# mainSchematic.net
KiCad netlist of a schematic drawn in Altium Designer
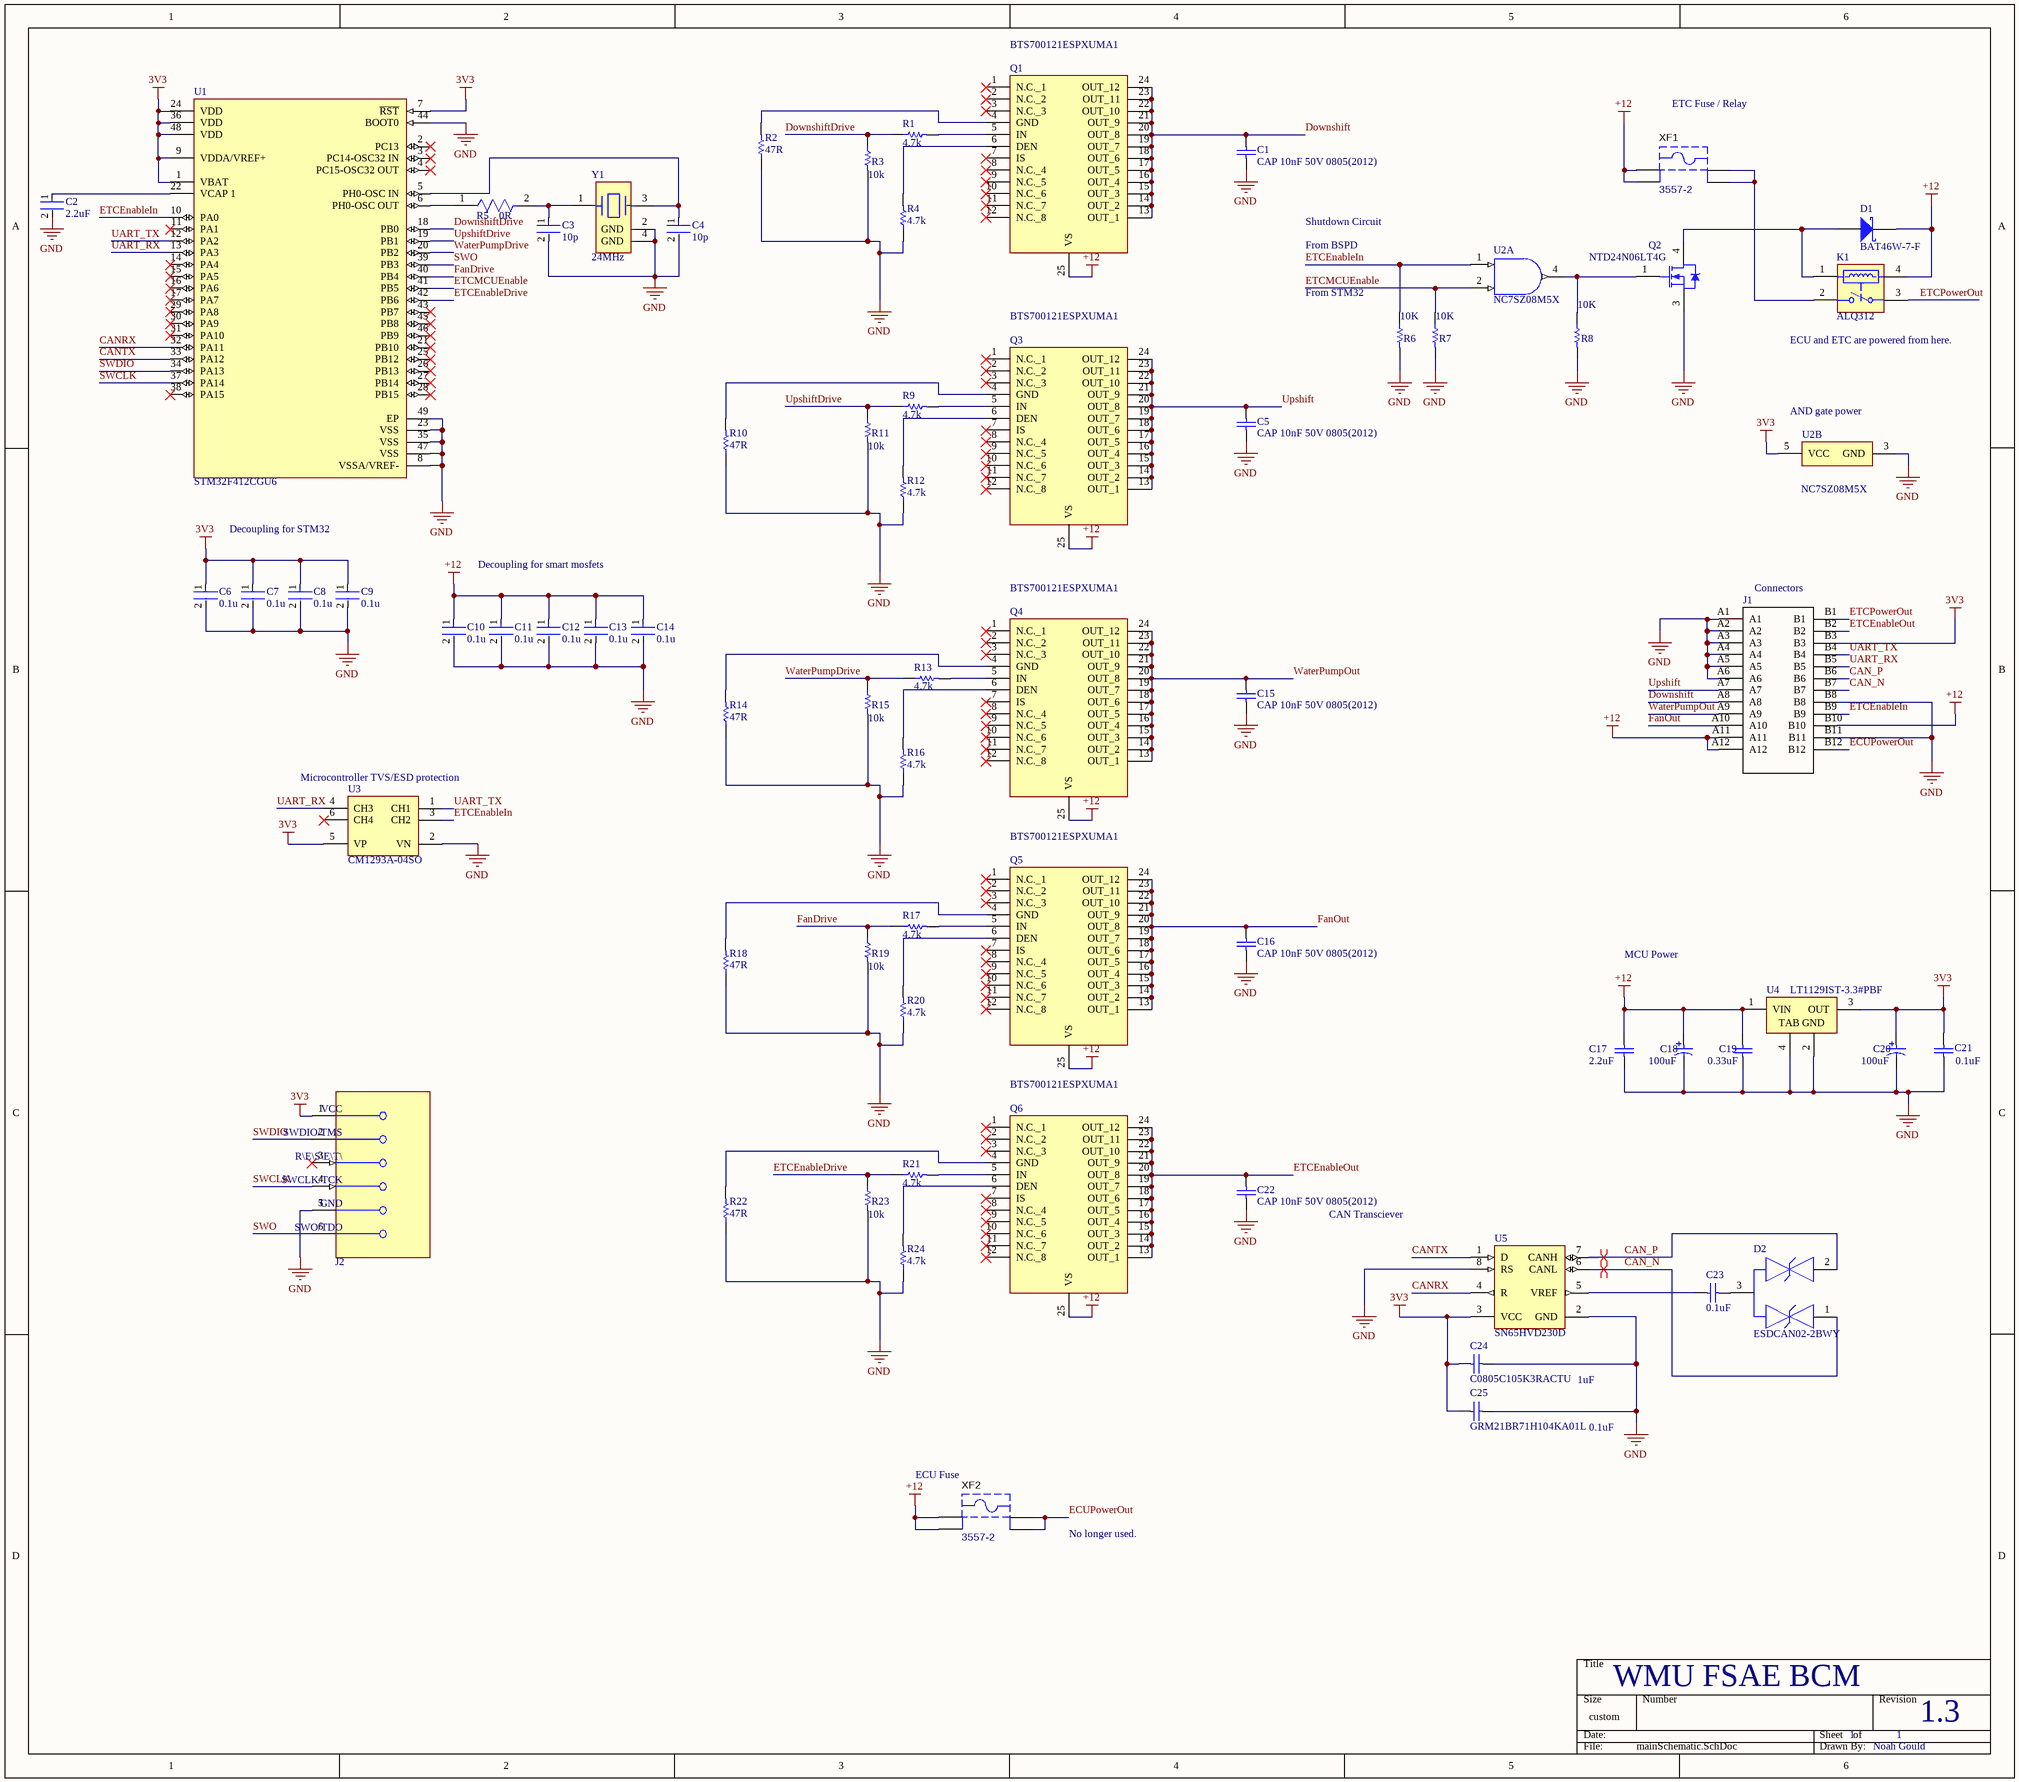
[diagram p0: mainSchematic.SchDoc]

(export (version "E")
  (design (tool "Eeschema 10.0.6"))
  (components
    (comp (ref "C1")
      (value "CAP 10nF 50V 0805(2012)")
      (footprint "CAPC0805(2012)75_N")
      (description "CAP 10nF 50V ±5% 0805 (2012 Metric) Thickness 0.75mm SMD")
      (fields (field (name "TOLERANCE") "Â±5%"))
      (libsource (lib "Altium Content Vault") (part "CAP"))
    )
    (comp (ref "C2")
      (value "2.2uF")
      (footprint "FP-GRM188-0_1-e0_2_0_5-MFG")
      (description "Chip Multilayer Ceramic Capacitors for General Purpose, 0603, 2.2uF, X7R, 15%, 10%, 10V")
      (fields (field (name "VOLTAGE") "10V") (field (name "TOLERANCE") "10%"))
      (libsource (lib "Altium Content Vault") (part "11868f565c42a9108669ba33697ecf6"))
    )
    (comp (ref "C3")
      (value "10p")
      (footprint "FP-0603-L_1_6_0_15-W_0_81-IPC_C")
      (description "General Purpose Ceramic Capacitor, 0603, 10pF, 10%, NP0, 30ppm/°C, 50V")
      (fields (field (name "TOLERANCE") "10%") (field (name "VOLTAGE") "50V"))
      (libsource (lib "Altium Content Vault") (part "02cd4be3c70576c341d710602a673aa"))
    )
    (comp (ref "C4")
      (value "10p")
      (footprint "FP-0603-L_1_6_0_15-W_0_81-IPC_C")
      (description "General Purpose Ceramic Capacitor, 0603, 10pF, 10%, NP0, 30ppm/°C, 50V")
      (fields (field (name "TOLERANCE") "10%") (field (name "VOLTAGE") "50V"))
      (libsource (lib "Altium Content Vault") (part "02cd4be3c70576c341d710602a673aa"))
    )
    (comp (ref "C5")
      (value "CAP 10nF 50V 0805(2012)")
      (footprint "CAPC0805(2012)75_N")
      (description "CAP 10nF 50V ±5% 0805 (2012 Metric) Thickness 0.75mm SMD")
      (fields (field (name "TOLERANCE") "Â±5%"))
      (libsource (lib "Altium Content Vault") (part "CAP"))
    )
    (comp (ref "C6")
      (value "0.1u")
      (footprint "FP-C0603C-CF-MFG")
      (description "CAP CER 0.1UF 50V X7R 0603")
      (fields (field (name "TOLERANCE") "0.1") (field (name "MANUFACTURER") "KEMET"))
      (libsource (lib "Altium Content Vault") (part "b4654b650e69147ec39a6b967a45e02"))
    )
    (comp (ref "C7")
      (value "0.1u")
      (footprint "FP-C0603C-CF-MFG")
      (description "CAP CER 0.1UF 50V X7R 0603")
      (fields (field (name "TOLERANCE") "0.1") (field (name "MANUFACTURER") "KEMET"))
      (libsource (lib "Altium Content Vault") (part "b4654b650e69147ec39a6b967a45e02"))
    )
    (comp (ref "C8")
      (value "0.1u")
      (footprint "FP-C0603C-CF-MFG")
      (description "CAP CER 0.1UF 50V X7R 0603")
      (fields (field (name "TOLERANCE") "0.1") (field (name "MANUFACTURER") "KEMET"))
      (libsource (lib "Altium Content Vault") (part "b4654b650e69147ec39a6b967a45e02"))
    )
    (comp (ref "C9")
      (value "0.1u")
      (footprint "FP-C0603C-CF-MFG")
      (description "CAP CER 0.1UF 50V X7R 0603")
      (fields (field (name "TOLERANCE") "0.1") (field (name "MANUFACTURER") "KEMET"))
      (libsource (lib "Altium Content Vault") (part "b4654b650e69147ec39a6b967a45e02"))
    )
    (comp (ref "C10")
      (value "0.1u")
      (footprint "FP-C0603C-CF-MFG")
      (description "CAP CER 0.1UF 50V X7R 0603")
      (fields (field (name "TOLERANCE") "0.1") (field (name "MANUFACTURER") "KEMET"))
      (libsource (lib "Altium Content Vault") (part "b4654b650e69147ec39a6b967a45e02"))
    )
    (comp (ref "C11")
      (value "0.1u")
      (footprint "FP-C0603C-CF-MFG")
      (description "CAP CER 0.1UF 50V X7R 0603")
      (fields (field (name "TOLERANCE") "0.1") (field (name "MANUFACTURER") "KEMET"))
      (libsource (lib "Altium Content Vault") (part "b4654b650e69147ec39a6b967a45e02"))
    )
    (comp (ref "C12")
      (value "0.1u")
      (footprint "FP-C0603C-CF-MFG")
      (description "CAP CER 0.1UF 50V X7R 0603")
      (fields (field (name "TOLERANCE") "0.1") (field (name "MANUFACTURER") "KEMET"))
      (libsource (lib "Altium Content Vault") (part "b4654b650e69147ec39a6b967a45e02"))
    )
    (comp (ref "C13")
      (value "0.1u")
      (footprint "FP-C0603C-CF-MFG")
      (description "CAP CER 0.1UF 50V X7R 0603")
      (fields (field (name "TOLERANCE") "0.1") (field (name "MANUFACTURER") "KEMET"))
      (libsource (lib "Altium Content Vault") (part "b4654b650e69147ec39a6b967a45e02"))
    )
    (comp (ref "C14")
      (value "0.1u")
      (footprint "FP-C0603C-CF-MFG")
      (description "CAP CER 0.1UF 50V X7R 0603")
      (fields (field (name "TOLERANCE") "0.1") (field (name "MANUFACTURER") "KEMET"))
      (libsource (lib "Altium Content Vault") (part "b4654b650e69147ec39a6b967a45e02"))
    )
    (comp (ref "C15")
      (value "CAP 10nF 50V 0805(2012)")
      (footprint "CAPC0805(2012)75_N")
      (description "CAP 10nF 50V ±5% 0805 (2012 Metric) Thickness 0.75mm SMD")
      (fields (field (name "TOLERANCE") "Â±5%"))
      (libsource (lib "Altium Content Vault") (part "CAP"))
    )
    (comp (ref "C16")
      (value "CAP 10nF 50V 0805(2012)")
      (footprint "CAPC0805(2012)75_N")
      (description "CAP 10nF 50V ±5% 0805 (2012 Metric) Thickness 0.75mm SMD")
      (fields (field (name "TOLERANCE") "Â±5%"))
      (libsource (lib "Altium Content Vault") (part "CAP"))
    )
    (comp (ref "C17")
      (value "CAP 2.2uF 100V 1210(3225)")
      (footprint "CAPC1210(3225)280_N")
      (description "CAP 2.2uF 100V ±10% 1210 (3225 Metric) Thickness 2.8mm SMD")
      (fields (field (name "TOLERANCE") "Â±10%"))
      (libsource (lib "Altium Content Vault") (part "CAP"))
    )
    (comp (ref "C18")
      (value "EEEFK1H101P")
      (footprint "PNSC-FK-V-F_V")
      (fields (field (name "MANUFACTURER") "Panasonic"))
      (libsource (lib "Altium Content Vault") (part "CAP-P-2"))
    )
    (comp (ref "C19")
      (value "12065C334KAT2A")
      (footprint "CAPC3216X152X50LL20T25")
      (description "Chip Capacitor, 330 nF, +/- 10%, 50 V, -55 to 125 degC, 1206 (3216 Metric), RoHS, Tape and Reel")
      (fields (field (name "MANUFACTURER") "AVX"))
      (libsource (lib "Altium Content Vault") (part "CAP-NP-2"))
    )
    (comp (ref "C20")
      (value "EEEFK1H101P")
      (footprint "PNSC-FK-V-F_V")
      (fields (field (name "MANUFACTURER") "Panasonic"))
      (libsource (lib "Altium Content Vault") (part "CAP-P-2"))
    )
    (comp (ref "C21")
      (value "GRM21BR71H104KA01L")
      (footprint "CAPC2013X135X45ML10T25")
      (description "Chip Capacitor, 0.1 uF, +/- 10%, 50 V, -55 to 125 degC, 0805 (2012 Metric), RoHS, Tape and Reel")
      (fields (field (name "VOLTAGE") "50V") (field (name "TOLERANCE") "10%"))
      (libsource (lib "Altium Content Vault") (part "CAP-NP-2"))
    )
    (comp (ref "C22")
      (value "CAP 10nF 50V 0805(2012)")
      (footprint "CAPC0805(2012)75_N")
      (description "CAP 10nF 50V ±5% 0805 (2012 Metric) Thickness 0.75mm SMD")
      (fields (field (name "TOLERANCE") "Â±5%"))
      (libsource (lib "Altium Content Vault") (part "CAP"))
    )
    (comp (ref "C23")
      (value "0.1uF")
      (footprint "CAPC2013X135X45ML10T25")
      (description "Chip Capacitor, 0.1 uF, +/- 10%, 50 V, -55 to 125 degC, 0805 (2012 Metric), RoHS, Tape and Reel")
      (fields (field (name "VOLTAGE") "50V") (field (name "TOLERANCE") "10%"))
      (libsource (lib "Altium Content Vault") (part "CAP-NP-2"))
    )
    (comp (ref "C24")
      (value "C0805C105K3RACTU")
      (footprint "CAPC2013X140X50LL20T25")
      (fields (field (name "MANUFACTURER") "Kemet"))
      (libsource (lib "Altium Content Vault") (part "CAP"))
    )
    (comp (ref "C25")
      (value "GRM21BR71H104KA01L")
      (footprint "CAPC2013X135X45ML10T25")
      (description "Chip Capacitor, 0.1 uF, +/- 10%, 50 V, -55 to 125 degC, 0805 (2012 Metric), RoHS, Tape and Reel")
      (fields (field (name "VOLTAGE") "50V") (field (name "TOLERANCE") "10%"))
      (libsource (lib "Altium Content Vault") (part "CAP-NP-2"))
    )
    (comp (ref "D1")
      (value "BAT46W-7-F")
      (footprint "DIOD-SOD-123-2_V")
      (description "Surface Mount Schottky Barrier Diode, 100 V, -55 to 125 degC, 2-Pin SOD123, RoHS, Tape and Reel")
      (fields (field (name "MANUFACTURER") "Diodes Inc"))
      (libsource (lib "Altium Content Vault") (part "DIOD-DSKY-A1K2-2"))
    )
    (comp (ref "D2")
      (value "ESDCAN02-2BWY")
      (footprint "FP-SOT323-3L-MFG")
      (description "TVS DIODE 26.5V 44V SOT323-3")
      (fields
        (field (name "MANUFACTURER") "STMicroelectronics")
        (field (name "OCTOPART") "https://octopart.com/esdcan02-2bwy-stmicroelectronics-58631133")
      )
      (libsource (lib "Altium Content Vault") (part "0b9019fb5e52ed66df21ec1535be59d"))
    )
    (comp (ref "J1")
      (value "DTM1312PA12PBR008")
      (footprint "*TE_DTM1312PA12PBR008_DTM1312PA12PBR008(Primary)")
      (description "Double Header 24 pin receptacle")
      (fields (field (name "MP") "DTM13-12PA-12PB-R008") (field (name "MF") "TE Connectivity"))
      (libsource (lib "DTM1312PA12PBR008") (part "DTM1312PA12PBR008"))
    )
    (comp (ref "J2")
      (value "TC2030-CTX-NL")
      (footprint "Tag_Connect_0_MFG")
      (libsource (lib "Conn_Tag_Connect_TC2030-CTX-NL_eec") (part "TC2030-CTX-NL"))
    )
    (comp (ref "K1")
      (value "ALQ312")
      (footprint "PNSC-LQ-4-2000x1000x1600_V")
      (fields (field (name "MANUFACTURER") "Panasonic"))
      (libsource (lib "Altium Content Vault") (part "PNSC-ALQ312-LQ-4-2000x1000x1600-4"))
    )
    (comp (ref "Q1")
      (value "BTS700121ESPXUMA1")
      (footprint "SamacSys:SOP65P600X115-25N")
      (description "Integrated Circuit")
      (fields (field (name "MOUSER PART NUMBER") "726-BTS700121ESPXUMA"))
      (libsource (lib "*") (part "BTS700121ESPXUMA1"))
    )
    (comp (ref "Q2")
      (value "NTD24N06LT4G")
      (footprint "ONSC-DPAK-3-369C-01_V")
      (description "Power MOSFET, 24 A, 60 V, Logic Level, N-Channel, 3-Pin DPAK, Pb-Free, Tape and Reel")
      (fields (field (name "MANUFACTURER") "On Semiconductor"))
      (libsource (lib "Altium Content Vault") (part "ONSC-NMOS-G1S3D4-3_C"))
    )
    (comp (ref "Q3")
      (value "BTS700121ESPXUMA1")
      (footprint "SamacSys:SOP65P600X115-25N")
      (description "Integrated Circuit")
      (fields (field (name "MOUSER PART NUMBER") "726-BTS700121ESPXUMA"))
      (libsource (lib "*") (part "BTS700121ESPXUMA1"))
    )
    (comp (ref "Q4")
      (value "BTS700121ESPXUMA1")
      (footprint "SamacSys:SOP65P600X115-25N")
      (description "Integrated Circuit")
      (fields (field (name "MOUSER PART NUMBER") "726-BTS700121ESPXUMA"))
      (libsource (lib "*") (part "BTS700121ESPXUMA1"))
    )
    (comp (ref "Q5")
      (value "BTS700121ESPXUMA1")
      (footprint "SamacSys:SOP65P600X115-25N")
      (description "Integrated Circuit")
      (fields (field (name "MOUSER PART NUMBER") "726-BTS700121ESPXUMA"))
      (libsource (lib "*") (part "BTS700121ESPXUMA1"))
    )
    (comp (ref "Q6")
      (value "BTS700121ESPXUMA1")
      (footprint "SamacSys:SOP65P600X115-25N")
      (description "Integrated Circuit")
      (fields (field (name "MOUSER PART NUMBER") "726-BTS700121ESPXUMA"))
      (libsource (lib "*") (part "BTS700121ESPXUMA1"))
    )
    (comp (ref "R1")
      (value "4.7k")
      (footprint "RESC2013X70X40NL20T20")
      (description "Chip Resistor, 4.7 KOhm, +/- 1%, 0.125 W, -55 to 155 degC, 0805 (2012 Metric), RoHS, Tape and Reel")
      (fields (field (name "MANUFACTURER") "Panasonic"))
      (libsource (lib "Altium Content Vault") (part "RES-2"))
    )
    (comp (ref "R2")
      (value "47R")
      (footprint "RESC2013X70X40NL20T20")
      (fields (field (name "PART NUMBER") "ERJ6ENF47R0V") (field (name "MANUFACTURER") "Panasonic"))
      (libsource (lib "Altium Content Vault") (part "RES"))
    )
    (comp (ref "R3")
      (value "10k")
      (footprint "RESC3216X70X50LL20T25")
      (fields (field (name "MANUFACTURER") "Panasonic") (field (name "PART NUMBER") "ERA8AEB103V"))
      (libsource (lib "Altium Content Vault") (part "RES"))
    )
    (comp (ref "R4")
      (value "4.7k")
      (footprint "RESC2013X70X40NL20T20")
      (description "Chip Resistor, 4.7 KOhm, +/- 1%, 0.125 W, -55 to 155 degC, 0805 (2012 Metric), RoHS, Tape and Reel")
      (fields (field (name "MANUFACTURER") "Panasonic"))
      (libsource (lib "Altium Content Vault") (part "RES-2"))
    )
    (comp (ref "R5")
      (value "0R")
      (footprint "FP-RC0603-MFG")
      (description "RES SMD 0 OHM JUMPER 1/10W 0603")
      (fields
        (field (name "TOLERANCE") "1%")
        (field (name "OCTOPART") "https://octopart.com/rc0603fr-070rl-yageo-1180803")
      )
      (libsource (lib "Altium Content Vault") (part "1029c3af85768c4190bb7ad29bc67b5"))
    )
    (comp (ref "R6")
      (value "ERA8AEB103V")
      (footprint "RESC3216X70X50LL20T25")
      (fields (field (name "MANUFACTURER") "Panasonic"))
      (libsource (lib "Altium Content Vault") (part "RES"))
    )
    (comp (ref "R7")
      (value "ERA8AEB103V")
      (footprint "RESC3216X70X50LL20T25")
      (fields (field (name "MANUFACTURER") "Panasonic"))
      (libsource (lib "Altium Content Vault") (part "RES"))
    )
    (comp (ref "R8")
      (value "ERA8AEB103V")
      (footprint "RESC3216X70X50LL20T25")
      (fields (field (name "MANUFACTURER") "Panasonic"))
      (libsource (lib "Altium Content Vault") (part "RES"))
    )
    (comp (ref "R9")
      (value "4.7k")
      (footprint "RESC2013X70X40NL20T20")
      (description "Chip Resistor, 4.7 KOhm, +/- 1%, 0.125 W, -55 to 155 degC, 0805 (2012 Metric), RoHS, Tape and Reel")
      (fields (field (name "MANUFACTURER") "Panasonic"))
      (libsource (lib "Altium Content Vault") (part "RES-2"))
    )
    (comp (ref "R10")
      (value "47R")
      (footprint "RESC2013X70X40NL20T20")
      (fields (field (name "PART NUMBER") "ERJ6ENF47R0V") (field (name "MANUFACTURER") "Panasonic"))
      (libsource (lib "Altium Content Vault") (part "RES"))
    )
    (comp (ref "R11")
      (value "10k")
      (footprint "RESC3216X70X50LL20T25")
      (fields (field (name "MANUFACTURER") "Panasonic") (field (name "PART NUMBER") "ERA8AEB103V"))
      (libsource (lib "Altium Content Vault") (part "RES"))
    )
    (comp (ref "R12")
      (value "4.7k")
      (footprint "RESC2013X70X40NL20T20")
      (description "Chip Resistor, 4.7 KOhm, +/- 1%, 0.125 W, -55 to 155 degC, 0805 (2012 Metric), RoHS, Tape and Reel")
      (fields (field (name "MANUFACTURER") "Panasonic"))
      (libsource (lib "Altium Content Vault") (part "RES-2"))
    )
    (comp (ref "R13")
      (value "4.7k")
      (footprint "RESC2013X70X40NL20T20")
      (description "Chip Resistor, 4.7 KOhm, +/- 1%, 0.125 W, -55 to 155 degC, 0805 (2012 Metric), RoHS, Tape and Reel")
      (fields (field (name "MANUFACTURER") "Panasonic"))
      (libsource (lib "Altium Content Vault") (part "RES-2"))
    )
    (comp (ref "R14")
      (value "47R")
      (footprint "RESC2013X70X40NL20T20")
      (fields (field (name "PART NUMBER") "ERJ6ENF47R0V") (field (name "MANUFACTURER") "Panasonic"))
      (libsource (lib "Altium Content Vault") (part "RES"))
    )
    (comp (ref "R15")
      (value "10k")
      (footprint "RESC3216X70X50LL20T25")
      (fields (field (name "MANUFACTURER") "Panasonic") (field (name "PART NUMBER") "ERA8AEB103V"))
      (libsource (lib "Altium Content Vault") (part "RES"))
    )
    (comp (ref "R16")
      (value "4.7k")
      (footprint "RESC2013X70X40NL20T20")
      (description "Chip Resistor, 4.7 KOhm, +/- 1%, 0.125 W, -55 to 155 degC, 0805 (2012 Metric), RoHS, Tape and Reel")
      (fields (field (name "MANUFACTURER") "Panasonic"))
      (libsource (lib "Altium Content Vault") (part "RES-2"))
    )
    (comp (ref "R17")
      (value "4.7k")
      (footprint "RESC2013X70X40NL20T20")
      (description "Chip Resistor, 4.7 KOhm, +/- 1%, 0.125 W, -55 to 155 degC, 0805 (2012 Metric), RoHS, Tape and Reel")
      (fields (field (name "MANUFACTURER") "Panasonic"))
      (libsource (lib "Altium Content Vault") (part "RES-2"))
    )
    (comp (ref "R18")
      (value "47R")
      (footprint "RESC2013X70X40NL20T20")
      (fields (field (name "PART NUMBER") "ERJ6ENF47R0V") (field (name "MANUFACTURER") "Panasonic"))
      (libsource (lib "Altium Content Vault") (part "RES"))
    )
    (comp (ref "R19")
      (value "10k")
      (footprint "RESC3216X70X50LL20T25")
      (fields (field (name "MANUFACTURER") "Panasonic") (field (name "PART NUMBER") "ERA8AEB103V"))
      (libsource (lib "Altium Content Vault") (part "RES"))
    )
    (comp (ref "R20")
      (value "4.7k")
      (footprint "RESC2013X70X40NL20T20")
      (description "Chip Resistor, 4.7 KOhm, +/- 1%, 0.125 W, -55 to 155 degC, 0805 (2012 Metric), RoHS, Tape and Reel")
      (fields (field (name "MANUFACTURER") "Panasonic"))
      (libsource (lib "Altium Content Vault") (part "RES-2"))
    )
    (comp (ref "R21")
      (value "4.7k")
      (footprint "RESC2013X70X40NL20T20")
      (description "Chip Resistor, 4.7 KOhm, +/- 1%, 0.125 W, -55 to 155 degC, 0805 (2012 Metric), RoHS, Tape and Reel")
      (fields (field (name "MANUFACTURER") "Panasonic"))
      (libsource (lib "Altium Content Vault") (part "RES-2"))
    )
    (comp (ref "R22")
      (value "47R")
      (footprint "RESC2013X70X40NL20T20")
      (fields (field (name "PART NUMBER") "ERJ6ENF47R0V") (field (name "MANUFACTURER") "Panasonic"))
      (libsource (lib "Altium Content Vault") (part "RES"))
    )
    (comp (ref "R23")
      (value "10k")
      (footprint "RESC3216X70X50LL20T25")
      (fields (field (name "MANUFACTURER") "Panasonic") (field (name "PART NUMBER") "ERA8AEB103V"))
      (libsource (lib "Altium Content Vault") (part "RES"))
    )
    (comp (ref "R24")
      (value "4.7k")
      (footprint "RESC2013X70X40NL20T20")
      (description "Chip Resistor, 4.7 KOhm, +/- 1%, 0.125 W, -55 to 155 degC, 0805 (2012 Metric), RoHS, Tape and Reel")
      (fields (field (name "MANUFACTURER") "Panasonic"))
      (libsource (lib "Altium Content Vault") (part "RES-2"))
    )
    (comp (ref "U1")
      (value "STM32F412CGU6")
      (footprint "FP-UFQFPN48-A0B9-MFG")
      (description "IC MCU 32BIT 1MB FLASH 48UFQFPN")
      (libsource (lib "Altium Content Vault") (part "7dd92b861eb4b166e7106aa1111722c"))
    )
    (comp (ref "U2")
      (value "NC7SZ08M5X")
      (footprint "FAIR-SOT23-5_V")
      (description "TinyLogic(R) UHS 2-Input AND Gate, 1.65 to 5.5 V, -40 to 85 degC, 5-Pin SOT23, RoHS, Tape and Reel")
      (fields (field (name "MANUFACTURER") "FairchildSemiconductor"))
      (libsource (lib "Altium Content Vault") (part "AND-1-2IN-5"))
    )
    (comp (ref "U3")
      (value "CM1293A-04SO")
      (footprint "ONSC-SC-74-6-318F-05_V")
      (description "4-Channel Low Capacitance ESD Protection Array, 6-Pin SC-74, Pb-Free, Tape and Reel")
      (fields (field (name "MANUFACTURER") "On Semiconductor"))
      (libsource (lib "Altium Content Vault") (part "ONSC-CM12XX-6"))
    )
    (comp (ref "U4")
      (value "LT1129IST-3.3#PBF")
      (footprint "LT-ST-3-SOT-223_L")
      (fields (field (name "MANUFACTURER") "Linear Technology"))
      (libsource (lib "Altium Content Vault") (part "LT-LT112X-ST-3"))
    )
    (comp (ref "U5")
      (value "SN65HVD230D")
      (footprint "D0008A_M")
      (description "CAN Bus Transceiver, 3.3 V, -40 to 85 degC, 8-Pin SOIC (D), Green (RoHS & no Sb/Br), Tube")
      (fields (field (name "GENERIC PART NUMBER") "SN65HVD230"))
      (libsource (lib "Altium Content Vault") (part "TI-SN65HVD230D-SOIC_D-8"))
    )
    (comp (ref "XF1")
      (value "3557-2")
      (footprint "KSTN-3557-2")
      (description "FUSE HOLDER, PCB MOUNT, 500VAC, 20A, ROHS")
      (fields (field (name "VOLTAGE") "500V") (field (name "MANUFACTURER") "Keystone-Electronics"))
      (libsource (lib "Altium Content Vault") (part "FUSE_HOLDER-4"))
    )
    (comp (ref "XF2")
      (value "3557-2")
      (footprint "KSTN-3557-2")
      (description "FUSE HOLDER, PCB MOUNT, 500VAC, 20A, ROHS")
      (fields (field (name "VOLTAGE") "500V") (field (name "MANUFACTURER") "Keystone-Electronics"))
      (libsource (lib "Altium Content Vault") (part "FUSE_HOLDER-4"))
    )
    (comp (ref "Y1")
      (value "24MHz")
      (footprint "FP-7M-MFG")
      (description "Crystal 24MHz, 10ppm, 10pF, 50Ω")
      (fields (field (name "TOLERANCE") "10ppm"))
      (libsource (lib "Altium Content Vault") (part "41079aabb0e87794b56622915be14ed"))
    )
  )
  (nets
    (net (code "1") (name "+12") (class "Default")
      (node (ref "C10") (pin "1") (pinfunction "1_1") (pintype "passive"))
      (node (ref "C11") (pin "1") (pinfunction "1_1") (pintype "passive"))
      (node (ref "C12") (pin "1") (pinfunction "1_1") (pintype "passive"))
      (node (ref "C13") (pin "1") (pinfunction "1_1") (pintype "passive"))
      (node (ref "C14") (pin "1") (pinfunction "1_1") (pintype "passive"))
      (node (ref "C17") (pin "1") (pinfunction "1_1") (pintype "passive"))
      (node (ref "C18") (pin "1") (pinfunction "1_1") (pintype "passive"))
      (node (ref "C19") (pin "1") (pinfunction "1_1") (pintype "passive"))
      (node (ref "D1") (pin "2") (pinfunction "K_2") (pintype "passive"))
      (node (ref "J1") (pin "A11") (pinfunction "A11_A11") (pintype "passive"))
      (node (ref "J1") (pin "A12") (pinfunction "A12_A12") (pintype "passive"))
      (node (ref "J1") (pin "B10") (pinfunction "B10_B10") (pintype "passive"))
      (node (ref "K1") (pin "4") (pinfunction "4_4") (pintype "passive"))
      (node (ref "Q1") (pin "25") (pinfunction "VS_25") (pintype "passive"))
      (node (ref "Q3") (pin "25") (pinfunction "VS_25") (pintype "passive"))
      (node (ref "Q4") (pin "25") (pinfunction "VS_25") (pintype "passive"))
      (node (ref "Q5") (pin "25") (pinfunction "VS_25") (pintype "passive"))
      (node (ref "Q6") (pin "25") (pinfunction "VS_25") (pintype "passive"))
      (node (ref "U4") (pin "1") (pinfunction "VIN_1") (pintype "power_in"))
      (node (ref "XF1") (pin "1") (pinfunction "1_1") (pintype "passive"))
      (node (ref "XF1") (pin "2") (pinfunction "2_2") (pintype "passive"))
      (node (ref "XF2") (pin "1") (pinfunction "1_1") (pintype "passive"))
      (node (ref "XF2") (pin "2") (pinfunction "2_2") (pintype "passive"))
    )
    (net (code "2") (name "/CANRX") (class "Default")
      (node (ref "U1") (pin "32") (pinfunction "PA11_32") (pintype "bidirectional"))
      (node (ref "U5") (pin "4") (pinfunction "R_4") (pintype "output"))
    )
    (net (code "3") (name "/CANTX") (class "Default")
      (node (ref "U1") (pin "33") (pinfunction "PA12_33") (pintype "bidirectional"))
      (node (ref "U5") (pin "1") (pinfunction "D_1") (pintype "input"))
    )
    (net (code "4") (name "/CAN_N") (class "Default")
      (node (ref "D2") (pin "1") (pinfunction "1_1") (pintype "passive"))
      (node (ref "J1") (pin "B7") (pinfunction "B7_B7") (pintype "passive"))
      (node (ref "U5") (pin "6") (pinfunction "CANL_6") (pintype "bidirectional"))
    )
    (net (code "5") (name "/CAN_P") (class "Default")
      (node (ref "D2") (pin "2") (pinfunction "2_2") (pintype "passive"))
      (node (ref "J1") (pin "B6") (pinfunction "B6_B6") (pintype "passive"))
      (node (ref "U5") (pin "7") (pinfunction "CANH_7") (pintype "bidirectional"))
    )
    (net (code "6") (name "/Downshift") (class "Default")
      (node (ref "C1") (pin "2") (pinfunction "2_2") (pintype "passive"))
      (node (ref "J1") (pin "A8") (pinfunction "A8_A8") (pintype "passive"))
      (node (ref "Q1") (pin "13") (pinfunction "OUT_1_13") (pintype "passive"))
      (node (ref "Q1") (pin "14") (pinfunction "OUT_2_14") (pintype "passive"))
      (node (ref "Q1") (pin "15") (pinfunction "OUT_3_15") (pintype "passive"))
      (node (ref "Q1") (pin "16") (pinfunction "OUT_4_16") (pintype "passive"))
      (node (ref "Q1") (pin "17") (pinfunction "OUT_5_17") (pintype "passive"))
      (node (ref "Q1") (pin "18") (pinfunction "OUT_6_18") (pintype "passive"))
      (node (ref "Q1") (pin "19") (pinfunction "OUT_7_19") (pintype "passive"))
      (node (ref "Q1") (pin "20") (pinfunction "OUT_8_20") (pintype "passive"))
      (node (ref "Q1") (pin "21") (pinfunction "OUT_9_21") (pintype "passive"))
      (node (ref "Q1") (pin "22") (pinfunction "OUT_10_22") (pintype "passive"))
      (node (ref "Q1") (pin "23") (pinfunction "OUT_11_23") (pintype "passive"))
      (node (ref "Q1") (pin "24") (pinfunction "OUT_12_24") (pintype "passive"))
    )
    (net (code "7") (name "/DownshiftDrive") (class "Default")
      (node (ref "R1") (pin "1") (pinfunction "1_1") (pintype "passive"))
      (node (ref "R3") (pin "1") (pinfunction "1_1") (pintype "passive"))
      (node (ref "U1") (pin "18") (pinfunction "PB0_18") (pintype "bidirectional"))
    )
    (net (code "8") (name "/ECUPowerOut") (class "Default")
      (node (ref "J1") (pin "B12") (pinfunction "B12_B12") (pintype "passive"))
      (node (ref "XF2") (pin "3") (pinfunction "3_3") (pintype "passive"))
      (node (ref "XF2") (pin "4") (pinfunction "4_4") (pintype "passive"))
    )
    (net (code "9") (name "/ETCEnableDrive") (class "Default")
      (node (ref "R21") (pin "1") (pinfunction "1_1") (pintype "passive"))
      (node (ref "R23") (pin "1") (pinfunction "1_1") (pintype "passive"))
      (node (ref "U1") (pin "42") (pinfunction "PB6_42") (pintype "bidirectional"))
    )
    (net (code "10") (name "/ETCEnableIn") (class "Default")
      (node (ref "J1") (pin "B9") (pinfunction "B9_B9") (pintype "passive"))
      (node (ref "R6") (pin "1") (pinfunction "1_1") (pintype "passive"))
      (node (ref "U1") (pin "10") (pinfunction "PA0_10") (pintype "bidirectional"))
      (node (ref "U2") (pin "1") (pinfunction "A_1") (pintype "input"))
      (node (ref "U3") (pin "3") (pinfunction "CH2_3") (pintype "passive"))
    )
    (net (code "11") (name "/ETCEnableOut") (class "Default")
      (node (ref "C22") (pin "2") (pinfunction "2_2") (pintype "passive"))
      (node (ref "J1") (pin "B2") (pinfunction "B2_B2") (pintype "passive"))
      (node (ref "Q6") (pin "13") (pinfunction "OUT_1_13") (pintype "passive"))
      (node (ref "Q6") (pin "14") (pinfunction "OUT_2_14") (pintype "passive"))
      (node (ref "Q6") (pin "15") (pinfunction "OUT_3_15") (pintype "passive"))
      (node (ref "Q6") (pin "16") (pinfunction "OUT_4_16") (pintype "passive"))
      (node (ref "Q6") (pin "17") (pinfunction "OUT_5_17") (pintype "passive"))
      (node (ref "Q6") (pin "18") (pinfunction "OUT_6_18") (pintype "passive"))
      (node (ref "Q6") (pin "19") (pinfunction "OUT_7_19") (pintype "passive"))
      (node (ref "Q6") (pin "20") (pinfunction "OUT_8_20") (pintype "passive"))
      (node (ref "Q6") (pin "21") (pinfunction "OUT_9_21") (pintype "passive"))
      (node (ref "Q6") (pin "22") (pinfunction "OUT_10_22") (pintype "passive"))
      (node (ref "Q6") (pin "23") (pinfunction "OUT_11_23") (pintype "passive"))
      (node (ref "Q6") (pin "24") (pinfunction "OUT_12_24") (pintype "passive"))
    )
    (net (code "12") (name "/ETCMCUEnable") (class "Default")
      (node (ref "R7") (pin "1") (pinfunction "1_1") (pintype "passive"))
      (node (ref "U1") (pin "41") (pinfunction "PB5_41") (pintype "bidirectional"))
      (node (ref "U2") (pin "2") (pinfunction "B_2") (pintype "input"))
    )
    (net (code "13") (name "/ETCPowerOut") (class "Default")
      (node (ref "J1") (pin "B1") (pinfunction "B1_B1") (pintype "passive"))
      (node (ref "K1") (pin "3") (pinfunction "COM_3") (pintype "passive"))
    )
    (net (code "14") (name "/FanDrive") (class "Default")
      (node (ref "R17") (pin "1") (pinfunction "1_1") (pintype "passive"))
      (node (ref "R19") (pin "1") (pinfunction "1_1") (pintype "passive"))
      (node (ref "U1") (pin "40") (pinfunction "PB4_40") (pintype "bidirectional"))
    )
    (net (code "15") (name "/FanOut") (class "Default")
      (node (ref "C16") (pin "2") (pinfunction "2_2") (pintype "passive"))
      (node (ref "J1") (pin "A10") (pinfunction "A10_A10") (pintype "passive"))
      (node (ref "Q5") (pin "13") (pinfunction "OUT_1_13") (pintype "passive"))
      (node (ref "Q5") (pin "14") (pinfunction "OUT_2_14") (pintype "passive"))
      (node (ref "Q5") (pin "15") (pinfunction "OUT_3_15") (pintype "passive"))
      (node (ref "Q5") (pin "16") (pinfunction "OUT_4_16") (pintype "passive"))
      (node (ref "Q5") (pin "17") (pinfunction "OUT_5_17") (pintype "passive"))
      (node (ref "Q5") (pin "18") (pinfunction "OUT_6_18") (pintype "passive"))
      (node (ref "Q5") (pin "19") (pinfunction "OUT_7_19") (pintype "passive"))
      (node (ref "Q5") (pin "20") (pinfunction "OUT_8_20") (pintype "passive"))
      (node (ref "Q5") (pin "21") (pinfunction "OUT_9_21") (pintype "passive"))
      (node (ref "Q5") (pin "22") (pinfunction "OUT_10_22") (pintype "passive"))
      (node (ref "Q5") (pin "23") (pinfunction "OUT_11_23") (pintype "passive"))
      (node (ref "Q5") (pin "24") (pinfunction "OUT_12_24") (pintype "passive"))
    )
    (net (code "16") (name "/SWCLK") (class "Default")
      (node (ref "J2") (pin "4") (pinfunction "SWCLK/TCK_4") (pintype "input"))
      (node (ref "U1") (pin "37") (pinfunction "PA14_37") (pintype "bidirectional"))
    )
    (net (code "17") (name "/SWDIO") (class "Default")
      (node (ref "J2") (pin "2") (pinfunction "SWDIO/TMS_2") (pintype "passive"))
      (node (ref "U1") (pin "34") (pinfunction "PA13_34") (pintype "bidirectional"))
    )
    (net (code "18") (name "/SWO") (class "Default")
      (node (ref "J2") (pin "6") (pinfunction "SWO/TDO_6") (pintype "passive"))
      (node (ref "U1") (pin "39") (pinfunction "PB3_39") (pintype "bidirectional"))
    )
    (net (code "19") (name "/UART_RX") (class "Default")
      (node (ref "J1") (pin "B5") (pinfunction "B5_B5") (pintype "passive"))
      (node (ref "U1") (pin "13") (pinfunction "PA3_13") (pintype "bidirectional"))
      (node (ref "U3") (pin "4") (pinfunction "CH3_4") (pintype "passive"))
    )
    (net (code "20") (name "/UART_TX") (class "Default")
      (node (ref "J1") (pin "B4") (pinfunction "B4_B4") (pintype "passive"))
      (node (ref "U1") (pin "12") (pinfunction "PA2_12") (pintype "bidirectional"))
      (node (ref "U3") (pin "1") (pinfunction "CH1_1") (pintype "passive"))
    )
    (net (code "21") (name "/Upshift") (class "Default")
      (node (ref "C5") (pin "2") (pinfunction "2_2") (pintype "passive"))
      (node (ref "J1") (pin "A7") (pinfunction "A7_A7") (pintype "passive"))
      (node (ref "Q3") (pin "13") (pinfunction "OUT_1_13") (pintype "passive"))
      (node (ref "Q3") (pin "14") (pinfunction "OUT_2_14") (pintype "passive"))
      (node (ref "Q3") (pin "15") (pinfunction "OUT_3_15") (pintype "passive"))
      (node (ref "Q3") (pin "16") (pinfunction "OUT_4_16") (pintype "passive"))
      (node (ref "Q3") (pin "17") (pinfunction "OUT_5_17") (pintype "passive"))
      (node (ref "Q3") (pin "18") (pinfunction "OUT_6_18") (pintype "passive"))
      (node (ref "Q3") (pin "19") (pinfunction "OUT_7_19") (pintype "passive"))
      (node (ref "Q3") (pin "20") (pinfunction "OUT_8_20") (pintype "passive"))
      (node (ref "Q3") (pin "21") (pinfunction "OUT_9_21") (pintype "passive"))
      (node (ref "Q3") (pin "22") (pinfunction "OUT_10_22") (pintype "passive"))
      (node (ref "Q3") (pin "23") (pinfunction "OUT_11_23") (pintype "passive"))
      (node (ref "Q3") (pin "24") (pinfunction "OUT_12_24") (pintype "passive"))
    )
    (net (code "22") (name "/UpshiftDrive") (class "Default")
      (node (ref "R11") (pin "1") (pinfunction "1_1") (pintype "passive"))
      (node (ref "R9") (pin "1") (pinfunction "1_1") (pintype "passive"))
      (node (ref "U1") (pin "19") (pinfunction "PB1_19") (pintype "bidirectional"))
    )
    (net (code "23") (name "/WaterPumpDrive") (class "Default")
      (node (ref "R13") (pin "1") (pinfunction "1_1") (pintype "passive"))
      (node (ref "R15") (pin "1") (pinfunction "1_1") (pintype "passive"))
      (node (ref "U1") (pin "20") (pinfunction "PB2_20") (pintype "bidirectional"))
    )
    (net (code "24") (name "/WaterPumpOut") (class "Default")
      (node (ref "C15") (pin "2") (pinfunction "2_2") (pintype "passive"))
      (node (ref "J1") (pin "A9") (pinfunction "A9_A9") (pintype "passive"))
      (node (ref "Q4") (pin "13") (pinfunction "OUT_1_13") (pintype "passive"))
      (node (ref "Q4") (pin "14") (pinfunction "OUT_2_14") (pintype "passive"))
      (node (ref "Q4") (pin "15") (pinfunction "OUT_3_15") (pintype "passive"))
      (node (ref "Q4") (pin "16") (pinfunction "OUT_4_16") (pintype "passive"))
      (node (ref "Q4") (pin "17") (pinfunction "OUT_5_17") (pintype "passive"))
      (node (ref "Q4") (pin "18") (pinfunction "OUT_6_18") (pintype "passive"))
      (node (ref "Q4") (pin "19") (pinfunction "OUT_7_19") (pintype "passive"))
      (node (ref "Q4") (pin "20") (pinfunction "OUT_8_20") (pintype "passive"))
      (node (ref "Q4") (pin "21") (pinfunction "OUT_9_21") (pintype "passive"))
      (node (ref "Q4") (pin "22") (pinfunction "OUT_10_22") (pintype "passive"))
      (node (ref "Q4") (pin "23") (pinfunction "OUT_11_23") (pintype "passive"))
      (node (ref "Q4") (pin "24") (pinfunction "OUT_12_24") (pintype "passive"))
    )
    (net (code "25") (name "3V3") (class "Default")
      (node (ref "C20") (pin "1") (pinfunction "1_1") (pintype "passive"))
      (node (ref "C21") (pin "1") (pinfunction "1_1") (pintype "passive"))
      (node (ref "C24") (pin "1") (pinfunction "1_1") (pintype "passive"))
      (node (ref "C25") (pin "1") (pinfunction "1_1") (pintype "passive"))
      (node (ref "C6") (pin "1") (pinfunction "1_1") (pintype "passive"))
      (node (ref "C7") (pin "1") (pinfunction "1_1") (pintype "passive"))
      (node (ref "C8") (pin "1") (pinfunction "1_1") (pintype "passive"))
      (node (ref "C9") (pin "1") (pinfunction "1_1") (pintype "passive"))
      (node (ref "J1") (pin "B3") (pinfunction "B3_B3") (pintype "passive"))
      (node (ref "J2") (pin "1") (pinfunction "VCC_1") (pintype "power_in"))
      (node (ref "U1") (pin "1") (pinfunction "VBAT_1") (pintype "power_in"))
      (node (ref "U1") (pin "24") (pinfunction "VDD_24") (pintype "power_in"))
      (node (ref "U1") (pin "36") (pinfunction "VDD_36") (pintype "power_in"))
      (node (ref "U1") (pin "48") (pinfunction "VDD_48") (pintype "power_in"))
      (node (ref "U1") (pin "7") (pinfunction "~{RST}_7") (pintype "input"))
      (node (ref "U1") (pin "9") (pinfunction "VDDA/VREF+_9") (pintype "power_in"))
      (node (ref "U2") (pin "5") (pinfunction "VCC_5") (pintype "power_in"))
      (node (ref "U3") (pin "5") (pinfunction "VP_5") (pintype "power_in"))
      (node (ref "U4") (pin "3") (pinfunction "OUT_3") (pintype "power_in"))
      (node (ref "U5") (pin "3") (pinfunction "VCC_3") (pintype "power_in"))
    )
    (net (code "26") (name "GND") (class "Default")
      (node (ref "C1") (pin "1") (pinfunction "1_1") (pintype "passive"))
      (node (ref "C10") (pin "2") (pinfunction "2_2") (pintype "passive"))
      (node (ref "C11") (pin "2") (pinfunction "2_2") (pintype "passive"))
      (node (ref "C12") (pin "2") (pinfunction "2_2") (pintype "passive"))
      (node (ref "C13") (pin "2") (pinfunction "2_2") (pintype "passive"))
      (node (ref "C14") (pin "2") (pinfunction "2_2") (pintype "passive"))
      (node (ref "C15") (pin "1") (pinfunction "1_1") (pintype "passive"))
      (node (ref "C16") (pin "1") (pinfunction "1_1") (pintype "passive"))
      (node (ref "C17") (pin "2") (pinfunction "2_2") (pintype "passive"))
      (node (ref "C18") (pin "2") (pinfunction "2_2") (pintype "passive"))
      (node (ref "C19") (pin "2") (pinfunction "2_2") (pintype "passive"))
      (node (ref "C2") (pin "2") (pinfunction "2_2") (pintype "passive"))
      (node (ref "C20") (pin "2") (pinfunction "2_2") (pintype "passive"))
      (node (ref "C21") (pin "2") (pinfunction "2_2") (pintype "passive"))
      (node (ref "C22") (pin "1") (pinfunction "1_1") (pintype "passive"))
      (node (ref "C24") (pin "2") (pinfunction "2_2") (pintype "passive"))
      (node (ref "C25") (pin "2") (pinfunction "2_2") (pintype "passive"))
      (node (ref "C3") (pin "2") (pinfunction "2_2") (pintype "passive"))
      (node (ref "C4") (pin "2") (pinfunction "2_2") (pintype "passive"))
      (node (ref "C5") (pin "1") (pinfunction "1_1") (pintype "passive"))
      (node (ref "C6") (pin "2") (pinfunction "2_2") (pintype "passive"))
      (node (ref "C7") (pin "2") (pinfunction "2_2") (pintype "passive"))
      (node (ref "C8") (pin "2") (pinfunction "2_2") (pintype "passive"))
      (node (ref "C9") (pin "2") (pinfunction "2_2") (pintype "passive"))
      (node (ref "J1") (pin "A1") (pinfunction "A1_A1") (pintype "passive"))
      (node (ref "J1") (pin "A2") (pinfunction "A2_A2") (pintype "passive"))
      (node (ref "J1") (pin "A3") (pinfunction "A3_A3") (pintype "passive"))
      (node (ref "J1") (pin "A4") (pinfunction "A4_A4") (pintype "passive"))
      (node (ref "J1") (pin "A5") (pinfunction "A5_A5") (pintype "passive"))
      (node (ref "J1") (pin "A6") (pinfunction "A6_A6") (pintype "passive"))
      (node (ref "J1") (pin "B11") (pinfunction "B11_B11") (pintype "passive"))
      (node (ref "J1") (pin "B8") (pinfunction "B8_B8") (pintype "passive"))
      (node (ref "J2") (pin "5") (pinfunction "GND_5") (pintype "power_in"))
      (node (ref "Q2") (pin "3") (pinfunction "S_3") (pintype "passive"))
      (node (ref "R10") (pin "1") (pinfunction "1_1") (pintype "passive"))
      (node (ref "R11") (pin "2") (pinfunction "2_2") (pintype "passive"))
      (node (ref "R12") (pin "1") (pinfunction "1_1") (pintype "passive"))
      (node (ref "R14") (pin "1") (pinfunction "1_1") (pintype "passive"))
      (node (ref "R15") (pin "2") (pinfunction "2_2") (pintype "passive"))
      (node (ref "R16") (pin "1") (pinfunction "1_1") (pintype "passive"))
      (node (ref "R18") (pin "1") (pinfunction "1_1") (pintype "passive"))
      (node (ref "R19") (pin "2") (pinfunction "2_2") (pintype "passive"))
      (node (ref "R2") (pin "1") (pinfunction "1_1") (pintype "passive"))
      (node (ref "R20") (pin "1") (pinfunction "1_1") (pintype "passive"))
      (node (ref "R22") (pin "1") (pinfunction "1_1") (pintype "passive"))
      (node (ref "R23") (pin "2") (pinfunction "2_2") (pintype "passive"))
      (node (ref "R24") (pin "1") (pinfunction "1_1") (pintype "passive"))
      (node (ref "R3") (pin "2") (pinfunction "2_2") (pintype "passive"))
      (node (ref "R4") (pin "1") (pinfunction "1_1") (pintype "passive"))
      (node (ref "R6") (pin "2") (pinfunction "2_2") (pintype "passive"))
      (node (ref "R7") (pin "2") (pinfunction "2_2") (pintype "passive"))
      (node (ref "R8") (pin "2") (pinfunction "2_2") (pintype "passive"))
      (node (ref "U1") (pin "23") (pinfunction "VSS_23") (pintype "power_in"))
      (node (ref "U1") (pin "35") (pinfunction "VSS_35") (pintype "power_in"))
      (node (ref "U1") (pin "44") (pinfunction "BOOT0_44") (pintype "input"))
      (node (ref "U1") (pin "47") (pinfunction "VSS_47") (pintype "power_in"))
      (node (ref "U1") (pin "49") (pinfunction "EP_49") (pintype "passive"))
      (node (ref "U1") (pin "8") (pinfunction "VSSA/VREF-_8") (pintype "power_in"))
      (node (ref "U2") (pin "3") (pinfunction "GND_3") (pintype "power_in"))
      (node (ref "U3") (pin "2") (pinfunction "VN_2") (pintype "power_in"))
      (node (ref "U4") (pin "2") (pinfunction "GND_2") (pintype "power_in"))
      (node (ref "U4") (pin "4") (pinfunction "TAB_4") (pintype "power_in"))
      (node (ref "U5") (pin "2") (pinfunction "GND_2") (pintype "power_in"))
      (node (ref "U5") (pin "8") (pinfunction "RS_8") (pintype "input"))
      (node (ref "Y1") (pin "2") (pinfunction "GND_2") (pintype "power_in"))
      (node (ref "Y1") (pin "4") (pinfunction "GND_4") (pintype "power_in"))
    )
    (net (code "27") (name "Net-(C3-Pad1)") (class "Default")
      (node (ref "C3") (pin "1") (pinfunction "1_1") (pintype "passive"))
      (node (ref "R5") (pin "2") (pinfunction "2_2") (pintype "passive"))
      (node (ref "Y1") (pin "1") (pinfunction "1_1") (pintype "passive"))
    )
    (net (code "28") (name "Net-(C23-Pad2)") (class "Default")
      (node (ref "C23") (pin "2") (pinfunction "2_2") (pintype "passive"))
      (node (ref "D2") (pin "3") (pinfunction "3_3") (pintype "passive"))
    )
    (net (code "29") (name "Net-(D1-A)") (class "Default")
      (node (ref "D1") (pin "1") (pinfunction "A_1") (pintype "passive"))
      (node (ref "K1") (pin "1") (pinfunction "1_1") (pintype "passive"))
      (node (ref "Q2") (pin "4") (pinfunction "D_4") (pintype "passive"))
    )
    (net (code "30") (name "Net-(K1-NO)") (class "Default")
      (node (ref "K1") (pin "2") (pinfunction "NO_2") (pintype "passive"))
      (node (ref "XF1") (pin "3") (pinfunction "3_3") (pintype "passive"))
      (node (ref "XF1") (pin "4") (pinfunction "4_4") (pintype "passive"))
    )
    (net (code "31") (name "Net-(Q1-DEN)") (class "Default")
      (node (ref "Q1") (pin "6") (pinfunction "DEN_6") (pintype "passive"))
      (node (ref "R4") (pin "2") (pinfunction "2_2") (pintype "passive"))
    )
    (net (code "32") (name "Net-(Q1-GND)") (class "Default")
      (node (ref "Q1") (pin "4") (pinfunction "GND_4") (pintype "passive"))
      (node (ref "R2") (pin "2") (pinfunction "2_2") (pintype "passive"))
    )
    (net (code "33") (name "Net-(Q1-IN)") (class "Default")
      (node (ref "Q1") (pin "5") (pinfunction "IN_5") (pintype "passive"))
      (node (ref "R1") (pin "2") (pinfunction "2_2") (pintype "passive"))
    )
    (net (code "34") (name "Net-(Q2-G)") (class "Default")
      (node (ref "Q2") (pin "1") (pinfunction "G_1") (pintype "passive"))
      (node (ref "R8") (pin "1") (pinfunction "1_1") (pintype "passive"))
      (node (ref "U2") (pin "4") (pinfunction "Y_4") (pintype "output"))
    )
    (net (code "35") (name "Net-(Q3-DEN)") (class "Default")
      (node (ref "Q3") (pin "6") (pinfunction "DEN_6") (pintype "passive"))
      (node (ref "R12") (pin "2") (pinfunction "2_2") (pintype "passive"))
    )
    (net (code "36") (name "Net-(Q3-GND)") (class "Default")
      (node (ref "Q3") (pin "4") (pinfunction "GND_4") (pintype "passive"))
      (node (ref "R10") (pin "2") (pinfunction "2_2") (pintype "passive"))
    )
    (net (code "37") (name "Net-(Q3-IN)") (class "Default")
      (node (ref "Q3") (pin "5") (pinfunction "IN_5") (pintype "passive"))
      (node (ref "R9") (pin "2") (pinfunction "2_2") (pintype "passive"))
    )
    (net (code "38") (name "Net-(Q4-DEN)") (class "Default")
      (node (ref "Q4") (pin "6") (pinfunction "DEN_6") (pintype "passive"))
      (node (ref "R16") (pin "2") (pinfunction "2_2") (pintype "passive"))
    )
    (net (code "39") (name "Net-(Q4-GND)") (class "Default")
      (node (ref "Q4") (pin "4") (pinfunction "GND_4") (pintype "passive"))
      (node (ref "R14") (pin "2") (pinfunction "2_2") (pintype "passive"))
    )
    (net (code "40") (name "Net-(Q4-IN)") (class "Default")
      (node (ref "Q4") (pin "5") (pinfunction "IN_5") (pintype "passive"))
      (node (ref "R13") (pin "2") (pinfunction "2_2") (pintype "passive"))
    )
    (net (code "41") (name "Net-(Q5-DEN)") (class "Default")
      (node (ref "Q5") (pin "6") (pinfunction "DEN_6") (pintype "passive"))
      (node (ref "R20") (pin "2") (pinfunction "2_2") (pintype "passive"))
    )
    (net (code "42") (name "Net-(Q5-GND)") (class "Default")
      (node (ref "Q5") (pin "4") (pinfunction "GND_4") (pintype "passive"))
      (node (ref "R18") (pin "2") (pinfunction "2_2") (pintype "passive"))
    )
    (net (code "43") (name "Net-(Q5-IN)") (class "Default")
      (node (ref "Q5") (pin "5") (pinfunction "IN_5") (pintype "passive"))
      (node (ref "R17") (pin "2") (pinfunction "2_2") (pintype "passive"))
    )
    (net (code "44") (name "Net-(Q6-DEN)") (class "Default")
      (node (ref "Q6") (pin "6") (pinfunction "DEN_6") (pintype "passive"))
      (node (ref "R24") (pin "2") (pinfunction "2_2") (pintype "passive"))
    )
    (net (code "45") (name "Net-(Q6-GND)") (class "Default")
      (node (ref "Q6") (pin "4") (pinfunction "GND_4") (pintype "passive"))
      (node (ref "R22") (pin "2") (pinfunction "2_2") (pintype "passive"))
    )
    (net (code "46") (name "Net-(Q6-IN)") (class "Default")
      (node (ref "Q6") (pin "5") (pinfunction "IN_5") (pintype "passive"))
      (node (ref "R21") (pin "2") (pinfunction "2_2") (pintype "passive"))
    )
    (net (code "47") (name "Net-(U1-PH0-OSC_IN)") (class "Default")
      (node (ref "C4") (pin "1") (pinfunction "1_1") (pintype "passive"))
      (node (ref "U1") (pin "5") (pinfunction "PH0-OSC_IN_5") (pintype "bidirectional"))
      (node (ref "Y1") (pin "3") (pinfunction "3_3") (pintype "passive"))
    )
    (net (code "48") (name "Net-(U1-PH0-OSC_OUT)") (class "Default")
      (node (ref "R5") (pin "1") (pinfunction "1_1") (pintype "passive"))
      (node (ref "U1") (pin "6") (pinfunction "PH0-OSC_OUT_6") (pintype "bidirectional"))
    )
    (net (code "49") (name "Net-(U1-VCAP_1)") (class "Default")
      (node (ref "C2") (pin "1") (pinfunction "1_1") (pintype "passive"))
      (node (ref "U1") (pin "22") (pinfunction "VCAP_1_22") (pintype "power_in"))
    )
    (net (code "50") (name "Net-(U5-VREF)") (class "Default")
      (node (ref "C23") (pin "1") (pinfunction "1_1") (pintype "passive"))
      (node (ref "U5") (pin "5") (pinfunction "VREF_5") (pintype "output"))
    )
    (net (code "51") (name "unconnected-(J2-~{RESET}-Pad3)") (class "Default")
      (node (ref "J2") (pin "3") (pinfunction "~{RESET}_3") (pintype "input+no_connect"))
    )
    (net (code "52") (name "unconnected-(Q1-IS-Pad7)") (class "Default")
      (node (ref "Q1") (pin "7") (pinfunction "IS_7") (pintype "passive+no_connect"))
    )
    (net (code "53") (name "unconnected-(Q1-N.C._1-Pad1)") (class "Default")
      (node (ref "Q1") (pin "1") (pinfunction "N.C._1_1") (pintype "passive+no_connect"))
    )
    (net (code "54") (name "unconnected-(Q1-N.C._2-Pad2)") (class "Default")
      (node (ref "Q1") (pin "2") (pinfunction "N.C._2_2") (pintype "passive+no_connect"))
    )
    (net (code "55") (name "unconnected-(Q1-N.C._3-Pad3)") (class "Default")
      (node (ref "Q1") (pin "3") (pinfunction "N.C._3_3") (pintype "passive+no_connect"))
    )
    (net (code "56") (name "unconnected-(Q1-N.C._4-Pad8)") (class "Default")
      (node (ref "Q1") (pin "8") (pinfunction "N.C._4_8") (pintype "passive+no_connect"))
    )
    (net (code "57") (name "unconnected-(Q1-N.C._5-Pad9)") (class "Default")
      (node (ref "Q1") (pin "9") (pinfunction "N.C._5_9") (pintype "passive+no_connect"))
    )
    (net (code "58") (name "unconnected-(Q1-N.C._6-Pad10)") (class "Default")
      (node (ref "Q1") (pin "10") (pinfunction "N.C._6_10") (pintype "passive+no_connect"))
    )
    (net (code "59") (name "unconnected-(Q1-N.C._7-Pad11)") (class "Default")
      (node (ref "Q1") (pin "11") (pinfunction "N.C._7_11") (pintype "passive+no_connect"))
    )
    (net (code "60") (name "unconnected-(Q1-N.C._8-Pad12)") (class "Default")
      (node (ref "Q1") (pin "12") (pinfunction "N.C._8_12") (pintype "passive+no_connect"))
    )
    (net (code "61") (name "unconnected-(Q3-IS-Pad7)") (class "Default")
      (node (ref "Q3") (pin "7") (pinfunction "IS_7") (pintype "passive+no_connect"))
    )
    (net (code "62") (name "unconnected-(Q3-N.C._1-Pad1)") (class "Default")
      (node (ref "Q3") (pin "1") (pinfunction "N.C._1_1") (pintype "passive+no_connect"))
    )
    (net (code "63") (name "unconnected-(Q3-N.C._2-Pad2)") (class "Default")
      (node (ref "Q3") (pin "2") (pinfunction "N.C._2_2") (pintype "passive+no_connect"))
    )
    (net (code "64") (name "unconnected-(Q3-N.C._3-Pad3)") (class "Default")
      (node (ref "Q3") (pin "3") (pinfunction "N.C._3_3") (pintype "passive+no_connect"))
    )
    (net (code "65") (name "unconnected-(Q3-N.C._4-Pad8)") (class "Default")
      (node (ref "Q3") (pin "8") (pinfunction "N.C._4_8") (pintype "passive+no_connect"))
    )
    (net (code "66") (name "unconnected-(Q3-N.C._5-Pad9)") (class "Default")
      (node (ref "Q3") (pin "9") (pinfunction "N.C._5_9") (pintype "passive+no_connect"))
    )
    (net (code "67") (name "unconnected-(Q3-N.C._6-Pad10)") (class "Default")
      (node (ref "Q3") (pin "10") (pinfunction "N.C._6_10") (pintype "passive+no_connect"))
    )
    (net (code "68") (name "unconnected-(Q3-N.C._7-Pad11)") (class "Default")
      (node (ref "Q3") (pin "11") (pinfunction "N.C._7_11") (pintype "passive+no_connect"))
    )
    (net (code "69") (name "unconnected-(Q3-N.C._8-Pad12)") (class "Default")
      (node (ref "Q3") (pin "12") (pinfunction "N.C._8_12") (pintype "passive+no_connect"))
    )
    (net (code "70") (name "unconnected-(Q4-IS-Pad7)") (class "Default")
      (node (ref "Q4") (pin "7") (pinfunction "IS_7") (pintype "passive+no_connect"))
    )
    (net (code "71") (name "unconnected-(Q4-N.C._1-Pad1)") (class "Default")
      (node (ref "Q4") (pin "1") (pinfunction "N.C._1_1") (pintype "passive+no_connect"))
    )
    (net (code "72") (name "unconnected-(Q4-N.C._2-Pad2)") (class "Default")
      (node (ref "Q4") (pin "2") (pinfunction "N.C._2_2") (pintype "passive+no_connect"))
    )
    (net (code "73") (name "unconnected-(Q4-N.C._3-Pad3)") (class "Default")
      (node (ref "Q4") (pin "3") (pinfunction "N.C._3_3") (pintype "passive+no_connect"))
    )
    (net (code "74") (name "unconnected-(Q4-N.C._4-Pad8)") (class "Default")
      (node (ref "Q4") (pin "8") (pinfunction "N.C._4_8") (pintype "passive+no_connect"))
    )
    (net (code "75") (name "unconnected-(Q4-N.C._5-Pad9)") (class "Default")
      (node (ref "Q4") (pin "9") (pinfunction "N.C._5_9") (pintype "passive+no_connect"))
    )
    (net (code "76") (name "unconnected-(Q4-N.C._6-Pad10)") (class "Default")
      (node (ref "Q4") (pin "10") (pinfunction "N.C._6_10") (pintype "passive+no_connect"))
    )
    (net (code "77") (name "unconnected-(Q4-N.C._7-Pad11)") (class "Default")
      (node (ref "Q4") (pin "11") (pinfunction "N.C._7_11") (pintype "passive+no_connect"))
    )
    (net (code "78") (name "unconnected-(Q4-N.C._8-Pad12)") (class "Default")
      (node (ref "Q4") (pin "12") (pinfunction "N.C._8_12") (pintype "passive+no_connect"))
    )
    (net (code "79") (name "unconnected-(Q5-IS-Pad7)") (class "Default")
      (node (ref "Q5") (pin "7") (pinfunction "IS_7") (pintype "passive+no_connect"))
    )
    (net (code "80") (name "unconnected-(Q5-N.C._1-Pad1)") (class "Default")
      (node (ref "Q5") (pin "1") (pinfunction "N.C._1_1") (pintype "passive+no_connect"))
    )
    (net (code "81") (name "unconnected-(Q5-N.C._2-Pad2)") (class "Default")
      (node (ref "Q5") (pin "2") (pinfunction "N.C._2_2") (pintype "passive+no_connect"))
    )
    (net (code "82") (name "unconnected-(Q5-N.C._3-Pad3)") (class "Default")
      (node (ref "Q5") (pin "3") (pinfunction "N.C._3_3") (pintype "passive+no_connect"))
    )
    (net (code "83") (name "unconnected-(Q5-N.C._4-Pad8)") (class "Default")
      (node (ref "Q5") (pin "8") (pinfunction "N.C._4_8") (pintype "passive+no_connect"))
    )
    (net (code "84") (name "unconnected-(Q5-N.C._5-Pad9)") (class "Default")
      (node (ref "Q5") (pin "9") (pinfunction "N.C._5_9") (pintype "passive+no_connect"))
    )
    (net (code "85") (name "unconnected-(Q5-N.C._6-Pad10)") (class "Default")
      (node (ref "Q5") (pin "10") (pinfunction "N.C._6_10") (pintype "passive+no_connect"))
    )
    (net (code "86") (name "unconnected-(Q5-N.C._7-Pad11)") (class "Default")
      (node (ref "Q5") (pin "11") (pinfunction "N.C._7_11") (pintype "passive+no_connect"))
    )
    (net (code "87") (name "unconnected-(Q5-N.C._8-Pad12)") (class "Default")
      (node (ref "Q5") (pin "12") (pinfunction "N.C._8_12") (pintype "passive+no_connect"))
    )
    (net (code "88") (name "unconnected-(Q6-IS-Pad7)") (class "Default")
      (node (ref "Q6") (pin "7") (pinfunction "IS_7") (pintype "passive+no_connect"))
    )
    (net (code "89") (name "unconnected-(Q6-N.C._1-Pad1)") (class "Default")
      (node (ref "Q6") (pin "1") (pinfunction "N.C._1_1") (pintype "passive+no_connect"))
    )
    (net (code "90") (name "unconnected-(Q6-N.C._2-Pad2)") (class "Default")
      (node (ref "Q6") (pin "2") (pinfunction "N.C._2_2") (pintype "passive+no_connect"))
    )
    (net (code "91") (name "unconnected-(Q6-N.C._3-Pad3)") (class "Default")
      (node (ref "Q6") (pin "3") (pinfunction "N.C._3_3") (pintype "passive+no_connect"))
    )
    (net (code "92") (name "unconnected-(Q6-N.C._4-Pad8)") (class "Default")
      (node (ref "Q6") (pin "8") (pinfunction "N.C._4_8") (pintype "passive+no_connect"))
    )
    (net (code "93") (name "unconnected-(Q6-N.C._5-Pad9)") (class "Default")
      (node (ref "Q6") (pin "9") (pinfunction "N.C._5_9") (pintype "passive+no_connect"))
    )
    (net (code "94") (name "unconnected-(Q6-N.C._6-Pad10)") (class "Default")
      (node (ref "Q6") (pin "10") (pinfunction "N.C._6_10") (pintype "passive+no_connect"))
    )
    (net (code "95") (name "unconnected-(Q6-N.C._7-Pad11)") (class "Default")
      (node (ref "Q6") (pin "11") (pinfunction "N.C._7_11") (pintype "passive+no_connect"))
    )
    (net (code "96") (name "unconnected-(Q6-N.C._8-Pad12)") (class "Default")
      (node (ref "Q6") (pin "12") (pinfunction "N.C._8_12") (pintype "passive+no_connect"))
    )
    (net (code "97") (name "unconnected-(U1-PA1-Pad11)") (class "Default")
      (node (ref "U1") (pin "11") (pinfunction "PA1_11") (pintype "bidirectional+no_connect"))
    )
    (net (code "98") (name "unconnected-(U1-PA4-Pad14)") (class "Default")
      (node (ref "U1") (pin "14") (pinfunction "PA4_14") (pintype "bidirectional+no_connect"))
    )
    (net (code "99") (name "unconnected-(U1-PA5-Pad15)") (class "Default")
      (node (ref "U1") (pin "15") (pinfunction "PA5_15") (pintype "bidirectional+no_connect"))
    )
    (net (code "100") (name "unconnected-(U1-PA6-Pad16)") (class "Default")
      (node (ref "U1") (pin "16") (pinfunction "PA6_16") (pintype "bidirectional+no_connect"))
    )
    (net (code "101") (name "unconnected-(U1-PA7-Pad17)") (class "Default")
      (node (ref "U1") (pin "17") (pinfunction "PA7_17") (pintype "bidirectional+no_connect"))
    )
    (net (code "102") (name "unconnected-(U1-PA8-Pad29)") (class "Default")
      (node (ref "U1") (pin "29") (pinfunction "PA8_29") (pintype "bidirectional+no_connect"))
    )
    (net (code "103") (name "unconnected-(U1-PA9-Pad30)") (class "Default")
      (node (ref "U1") (pin "30") (pinfunction "PA9_30") (pintype "bidirectional+no_connect"))
    )
    (net (code "104") (name "unconnected-(U1-PA10-Pad31)") (class "Default")
      (node (ref "U1") (pin "31") (pinfunction "PA10_31") (pintype "bidirectional+no_connect"))
    )
    (net (code "105") (name "unconnected-(U1-PA15-Pad38)") (class "Default")
      (node (ref "U1") (pin "38") (pinfunction "PA15_38") (pintype "bidirectional+no_connect"))
    )
    (net (code "106") (name "unconnected-(U1-PB7-Pad43)") (class "Default")
      (node (ref "U1") (pin "43") (pinfunction "PB7_43") (pintype "bidirectional+no_connect"))
    )
    (net (code "107") (name "unconnected-(U1-PB8-Pad45)") (class "Default")
      (node (ref "U1") (pin "45") (pinfunction "PB8_45") (pintype "bidirectional+no_connect"))
    )
    (net (code "108") (name "unconnected-(U1-PB9-Pad46)") (class "Default")
      (node (ref "U1") (pin "46") (pinfunction "PB9_46") (pintype "bidirectional+no_connect"))
    )
    (net (code "109") (name "unconnected-(U1-PB10-Pad21)") (class "Default")
      (node (ref "U1") (pin "21") (pinfunction "PB10_21") (pintype "bidirectional+no_connect"))
    )
    (net (code "110") (name "unconnected-(U1-PB12-Pad25)") (class "Default")
      (node (ref "U1") (pin "25") (pinfunction "PB12_25") (pintype "bidirectional+no_connect"))
    )
    (net (code "111") (name "unconnected-(U1-PB13-Pad26)") (class "Default")
      (node (ref "U1") (pin "26") (pinfunction "PB13_26") (pintype "bidirectional+no_connect"))
    )
    (net (code "112") (name "unconnected-(U1-PB14-Pad27)") (class "Default")
      (node (ref "U1") (pin "27") (pinfunction "PB14_27") (pintype "bidirectional+no_connect"))
    )
    (net (code "113") (name "unconnected-(U1-PB15-Pad28)") (class "Default")
      (node (ref "U1") (pin "28") (pinfunction "PB15_28") (pintype "bidirectional+no_connect"))
    )
    (net (code "114") (name "unconnected-(U1-PC13-Pad2)") (class "Default")
      (node (ref "U1") (pin "2") (pinfunction "PC13_2") (pintype "bidirectional+no_connect"))
    )
    (net (code "115") (name "unconnected-(U1-PC14-OSC32_IN-Pad3)") (class "Default")
      (node (ref "U1") (pin "3") (pinfunction "PC14-OSC32_IN_3") (pintype "bidirectional+no_connect"))
    )
    (net (code "116") (name "unconnected-(U1-PC15-OSC32_OUT-Pad4)") (class "Default")
      (node (ref "U1") (pin "4") (pinfunction "PC15-OSC32_OUT_4") (pintype "bidirectional+no_connect"))
    )
    (net (code "117") (name "unconnected-(U3-CH4-Pad6)") (class "Default")
      (node (ref "U3") (pin "6") (pinfunction "CH4_6") (pintype "passive+no_connect"))
    )
  )
)
